# design.net
KiCad netlist of a schematic drawn in Altium Designer
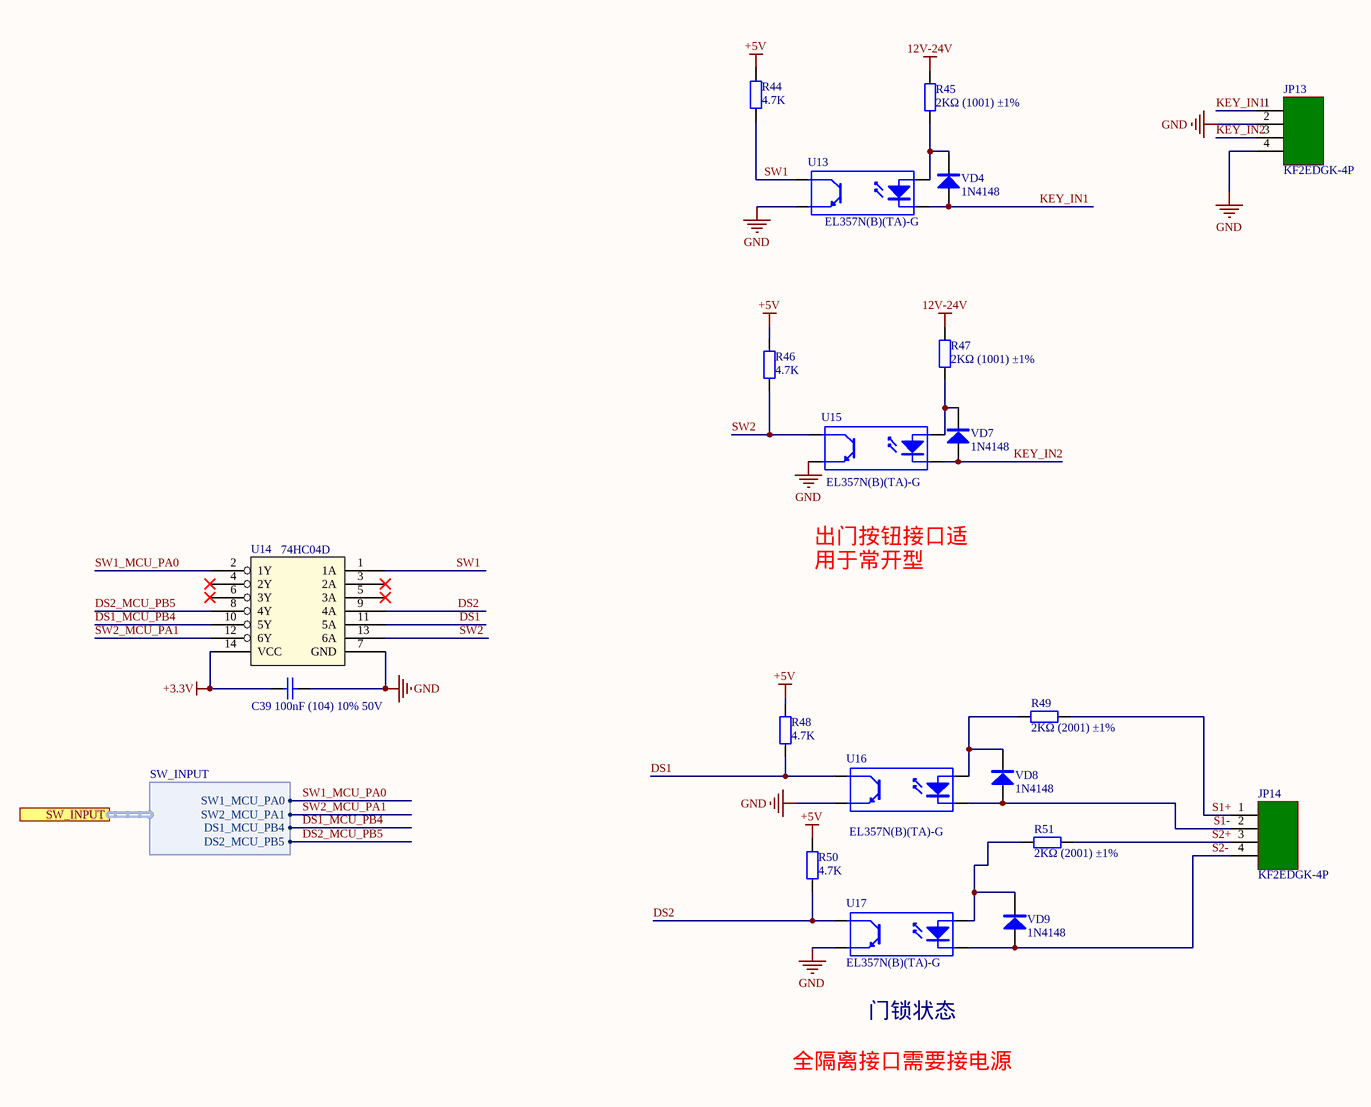
[diagram p0: 开关量输入.SchDoc]

(export (version "E")
  (design (tool "Eeschema 10.0.6"))
  (components
    (comp (ref "C39")
      (value "100nF (104) 10% 50V")
      (footprint "0603_C")
      (description "贴片电容")
      (libsource (lib "Miscellaneous Devices LC") (part "0603 100nF (104) 10% 50V"))
    )
    (comp (ref "JP13")
      (value "KF2EDGK-4P")
      (footprint "KF2EDGK5.08W-4P")
      (libsource (lib "KF2EDGK") (part "KF2EDGK-4P"))
    )
    (comp (ref "JP14")
      (value "KF2EDGK-4P")
      (footprint "KF2EDGK5.08W-4P")
      (libsource (lib "KF2EDGK") (part "KF2EDGK-4P"))
    )
    (comp (ref "R44")
      (value "4.7K")
      (footprint "0603_R")
      (description "贴片电阻")
      (libsource (lib "Miscellaneous Devices LC") (part "0603 1KΩ (1001) 1%"))
    )
    (comp (ref "R45")
      (value "2KΩ (1001) ±1%")
      (footprint "0603_R")
      (description "贴片电阻")
      (libsource (lib "Miscellaneous Devices LC") (part "0603 1KΩ (1001) 1%"))
    )
    (comp (ref "R46")
      (value "4.7K")
      (footprint "0603_R")
      (description "贴片电阻")
      (libsource (lib "Miscellaneous Devices LC") (part "0603 1KΩ (1001) 1%"))
    )
    (comp (ref "R47")
      (value "2KΩ (1001) ±1%")
      (footprint "0603_R")
      (description "贴片电阻")
      (libsource (lib "Miscellaneous Devices LC") (part "0603 1KΩ (1001) 1%"))
    )
    (comp (ref "R48")
      (value "4.7K")
      (footprint "0603_R")
      (description "贴片电阻")
      (libsource (lib "Miscellaneous Devices LC") (part "0603 1KΩ (1001) 1%"))
    )
    (comp (ref "R49")
      (value "2KΩ (2001) ±1%")
      (footprint "0805_R")
      (description "贴片电阻")
      (libsource (lib "Miscellaneous Devices LC") (part "0805 2KΩ (2001) 1%"))
    )
    (comp (ref "R50")
      (value "4.7K")
      (footprint "0603_R")
      (description "贴片电阻")
      (libsource (lib "Miscellaneous Devices LC") (part "0603 1KΩ (1001) 1%"))
    )
    (comp (ref "R51")
      (value "2KΩ (2001) ±1%")
      (footprint "0805_R")
      (description "贴片电阻")
      (libsource (lib "Miscellaneous Devices LC") (part "0805 2KΩ (2001) 1%"))
    )
    (comp (ref "U13")
      (value "EL357N(B)(TA)-G")
      (footprint "SOP-4_P2.54")
      (description "贴片光耦")
      (libsource (lib "Miscellaneous Devices LC") (part "EL357N(B)(TA)-G"))
    )
    (comp (ref "U14")
      (value "74HC04D")
      (footprint "SOIC-14_150mil")
      (description "反相器")
      (libsource (lib "KNX网关") (part "74HC04D"))
    )
    (comp (ref "U15")
      (value "EL357N(B)(TA)-G")
      (footprint "SOP-4_P2.54")
      (description "贴片光耦")
      (libsource (lib "Miscellaneous Devices LC") (part "EL357N(B)(TA)-G"))
    )
    (comp (ref "U16")
      (value "EL357N(B)(TA)-G")
      (footprint "SOP-4_P2.54")
      (description "贴片光耦")
      (libsource (lib "Miscellaneous Devices LC") (part "EL357N(B)(TA)-G"))
    )
    (comp (ref "U17")
      (value "EL357N(B)(TA)-G")
      (footprint "SOP-4_P2.54")
      (description "贴片光耦")
      (libsource (lib "Miscellaneous Devices LC") (part "EL357N(B)(TA)-G"))
    )
    (comp (ref "VD4")
      (value "1N4148")
      (footprint "MINI_MELF (LL34)")
      (description "高速开关二极管")
      (fields (field (name "版权归属") "源创客"))
      (libsource (lib "源创客") (part "1N4148"))
    )
    (comp (ref "VD7")
      (value "1N4148")
      (footprint "MINI_MELF (LL34)")
      (description "高速开关二极管")
      (fields (field (name "版权归属") "源创客"))
      (libsource (lib "源创客") (part "1N4148"))
    )
    (comp (ref "VD8")
      (value "1N4148")
      (footprint "MINI_MELF (LL34)")
      (description "高速开关二极管")
      (fields (field (name "版权归属") "源创客"))
      (libsource (lib "源创客") (part "1N4148"))
    )
    (comp (ref "VD9")
      (value "1N4148")
      (footprint "MINI_MELF (LL34)")
      (description "高速开关二极管")
      (fields (field (name "版权归属") "源创客"))
      (libsource (lib "源创客") (part "1N4148"))
    )
  )
  (nets
    (net (code "2") (name "+3.3V") (class "Default")
      (node (ref "C39") (pin "1") (pinfunction "1_1") (pintype "passive"))
      (node (ref "U14") (pin "14") (pinfunction "VCC_14") (pintype "power_in"))
    )
    (net (code "3") (name "+5V") (class "Default")
      (node (ref "R44") (pin "2") (pinfunction "2_2") (pintype "passive"))
      (node (ref "R46") (pin "2") (pinfunction "2_2") (pintype "passive"))
      (node (ref "R48") (pin "2") (pinfunction "2_2") (pintype "passive"))
      (node (ref "R50") (pin "2") (pinfunction "2_2") (pintype "passive"))
    )
    (net (code "4") (name "/DS1") (class "Default")
      (node (ref "R48") (pin "1") (pinfunction "1_1") (pintype "passive"))
      (node (ref "U14") (pin "11") (pinfunction "5A_11") (pintype "passive"))
      (node (ref "U16") (pin "4") (pinfunction "C_4") (pintype "passive"))
    )
    (net (code "5") (name "/DS1_MCU_PB4") (class "Default")
      (node (ref "U14") (pin "10") (pinfunction "5Y_10") (pintype "passive"))
    )
    (net (code "6") (name "/DS2") (class "Default")
      (node (ref "R50") (pin "1") (pinfunction "1_1") (pintype "passive"))
      (node (ref "U14") (pin "9") (pinfunction "4A_9") (pintype "passive"))
      (node (ref "U17") (pin "4") (pinfunction "C_4") (pintype "passive"))
    )
    (net (code "7") (name "/DS2_MCU_PB5") (class "Default")
      (node (ref "U14") (pin "8") (pinfunction "4Y_8") (pintype "passive"))
    )
    (net (code "8") (name "/KEY_IN1") (class "Default")
      (node (ref "JP13") (pin "1") (pinfunction "1_1") (pintype "passive"))
      (node (ref "U13") (pin "2") (pinfunction "K_2") (pintype "passive"))
      (node (ref "VD4") (pin "1") (pinfunction "A_1") (pintype "passive"))
    )
    (net (code "9") (name "/KEY_IN2") (class "Default")
      (node (ref "JP13") (pin "3") (pinfunction "3_3") (pintype "passive"))
      (node (ref "U15") (pin "2") (pinfunction "K_2") (pintype "passive"))
      (node (ref "VD7") (pin "1") (pinfunction "A_1") (pintype "passive"))
    )
    (net (code "10") (name "/S1+") (class "Default")
      (node (ref "JP14") (pin "1") (pinfunction "1_1") (pintype "passive"))
      (node (ref "R49") (pin "2") (pinfunction "2_2") (pintype "passive"))
    )
    (net (code "11") (name "/S1-") (class "Default")
      (node (ref "JP14") (pin "2") (pinfunction "2_2") (pintype "passive"))
      (node (ref "U16") (pin "2") (pinfunction "K_2") (pintype "passive"))
      (node (ref "VD8") (pin "1") (pinfunction "A_1") (pintype "passive"))
    )
    (net (code "12") (name "/S2+") (class "Default")
      (node (ref "JP14") (pin "3") (pinfunction "3_3") (pintype "passive"))
      (node (ref "R51") (pin "2") (pinfunction "2_2") (pintype "passive"))
    )
    (net (code "13") (name "/S2-") (class "Default")
      (node (ref "JP14") (pin "4") (pinfunction "4_4") (pintype "passive"))
      (node (ref "U17") (pin "2") (pinfunction "K_2") (pintype "passive"))
      (node (ref "VD9") (pin "1") (pinfunction "A_1") (pintype "passive"))
    )
    (net (code "14") (name "/SW1") (class "Default")
      (node (ref "R44") (pin "1") (pinfunction "1_1") (pintype "passive"))
      (node (ref "U13") (pin "4") (pinfunction "C_4") (pintype "passive"))
      (node (ref "U14") (pin "1") (pinfunction "1A_1") (pintype "passive"))
    )
    (net (code "15") (name "/SW1_MCU_PA0") (class "Default")
      (node (ref "U14") (pin "2") (pinfunction "1Y_2") (pintype "passive"))
    )
    (net (code "16") (name "/SW2") (class "Default")
      (node (ref "R46") (pin "1") (pinfunction "1_1") (pintype "passive"))
      (node (ref "U14") (pin "13") (pinfunction "6A_13") (pintype "passive"))
      (node (ref "U15") (pin "4") (pinfunction "C_4") (pintype "passive"))
    )
    (net (code "17") (name "/SW2_MCU_PA1") (class "Default")
      (node (ref "U14") (pin "12") (pinfunction "6Y_12") (pintype "passive"))
    )
    (net (code "19") (name "12V-24V") (class "Default")
      (node (ref "R45") (pin "2") (pinfunction "2_2") (pintype "passive"))
      (node (ref "R47") (pin "2") (pinfunction "2_2") (pintype "passive"))
    )
    (net (code "20") (name "GND") (class "Default")
      (node (ref "C39") (pin "2") (pinfunction "2_2") (pintype "passive"))
      (node (ref "JP13") (pin "2") (pinfunction "2_2") (pintype "passive"))
      (node (ref "JP13") (pin "4") (pinfunction "4_4") (pintype "passive"))
      (node (ref "U13") (pin "3") (pinfunction "E_3") (pintype "passive"))
      (node (ref "U14") (pin "7") (pinfunction "GND_7") (pintype "power_in"))
      (node (ref "U15") (pin "3") (pinfunction "E_3") (pintype "passive"))
      (node (ref "U16") (pin "3") (pinfunction "E_3") (pintype "passive"))
      (node (ref "U17") (pin "3") (pinfunction "E_3") (pintype "passive"))
    )
    (net (code "21") (name "Net-(U13-A)") (class "Default")
      (node (ref "R45") (pin "1") (pinfunction "1_1") (pintype "passive"))
      (node (ref "U13") (pin "1") (pinfunction "A_1") (pintype "passive"))
      (node (ref "VD4") (pin "2") (pinfunction "K_2") (pintype "passive"))
    )
    (net (code "22") (name "Net-(U15-A)") (class "Default")
      (node (ref "R47") (pin "1") (pinfunction "1_1") (pintype "passive"))
      (node (ref "U15") (pin "1") (pinfunction "A_1") (pintype "passive"))
      (node (ref "VD7") (pin "2") (pinfunction "K_2") (pintype "passive"))
    )
    (net (code "23") (name "Net-(U16-A)") (class "Default")
      (node (ref "R49") (pin "1") (pinfunction "1_1") (pintype "passive"))
      (node (ref "U16") (pin "1") (pinfunction "A_1") (pintype "passive"))
      (node (ref "VD8") (pin "2") (pinfunction "K_2") (pintype "passive"))
    )
    (net (code "24") (name "Net-(U17-A)") (class "Default")
      (node (ref "R51") (pin "1") (pinfunction "1_1") (pintype "passive"))
      (node (ref "U17") (pin "1") (pinfunction "A_1") (pintype "passive"))
      (node (ref "VD9") (pin "2") (pinfunction "K_2") (pintype "passive"))
    )
    (net (code "25") (name "unconnected-(U14-2A-Pad3)") (class "Default")
      (node (ref "U14") (pin "3") (pinfunction "2A_3") (pintype "passive+no_connect"))
    )
    (net (code "26") (name "unconnected-(U14-2Y-Pad4)") (class "Default")
      (node (ref "U14") (pin "4") (pinfunction "2Y_4") (pintype "passive+no_connect"))
    )
    (net (code "27") (name "unconnected-(U14-3A-Pad5)") (class "Default")
      (node (ref "U14") (pin "5") (pinfunction "3A_5") (pintype "passive+no_connect"))
    )
    (net (code "28") (name "unconnected-(U14-3Y-Pad6)") (class "Default")
      (node (ref "U14") (pin "6") (pinfunction "3Y_6") (pintype "passive+no_connect"))
    )
  )
)
